# M102X.net
KiCad netlist of a schematic drawn in EAGLE
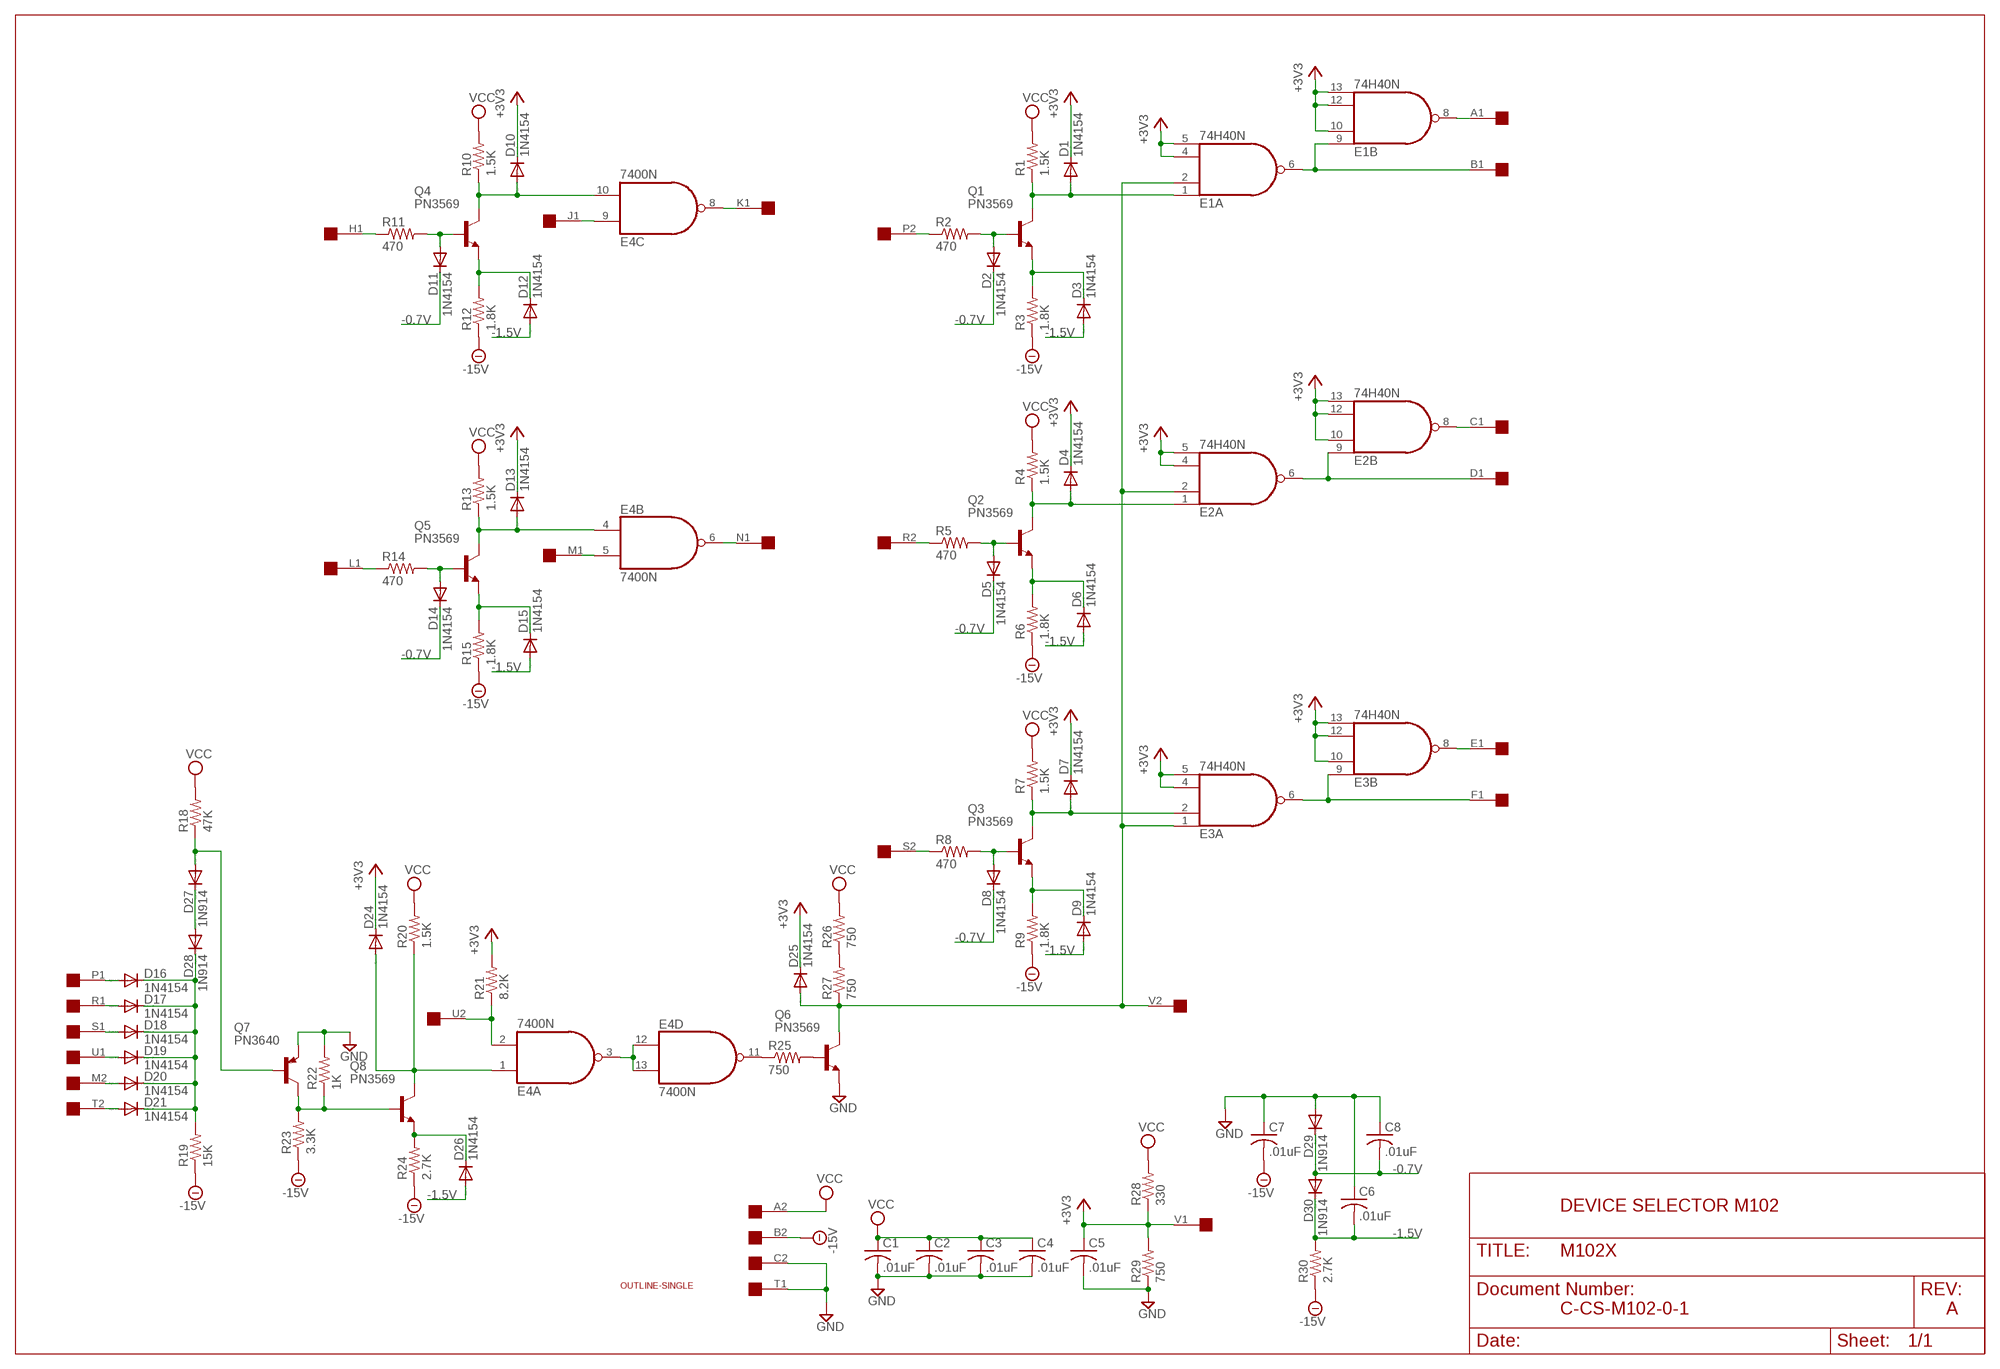
[diagram p0: schematic, sheet 1]

(export (version "E")
  (design (tool "Eeschema 10.0.6"))
  (components
    (comp (ref "C1")
      (value ".01uF")
      (footprint "eagle-import:C050-025X075")
      (libsource (lib "eagle-import") (part "C-US050-025X075"))
    )
    (comp (ref "C2")
      (value ".01uF")
      (footprint "eagle-import:C050-025X075")
      (libsource (lib "eagle-import") (part "C-US050-025X075"))
    )
    (comp (ref "C3")
      (value ".01uF")
      (footprint "eagle-import:C050-025X075")
      (libsource (lib "eagle-import") (part "C-US050-025X075"))
    )
    (comp (ref "C4")
      (value ".01uF")
      (footprint "eagle-import:C050-025X075")
      (libsource (lib "eagle-import") (part "C-US050-025X075"))
    )
    (comp (ref "C5")
      (value ".01uF")
      (footprint "eagle-import:C050-025X075")
      (libsource (lib "eagle-import") (part "C-US050-025X075"))
    )
    (comp (ref "C6")
      (value ".01uF")
      (footprint "eagle-import:C050-025X075")
      (libsource (lib "eagle-import") (part "C-US050-025X075"))
    )
    (comp (ref "C7")
      (value ".01uF")
      (footprint "eagle-import:C050-025X075")
      (libsource (lib "eagle-import") (part "C-US050-025X075"))
    )
    (comp (ref "C8")
      (value ".01uF")
      (footprint "eagle-import:C050-025X075")
      (libsource (lib "eagle-import") (part "C-US050-025X075"))
    )
    (comp (ref "D1")
      (value "1N4154")
      (footprint "eagle-import:DO35-10")
      (libsource (lib "eagle-import") (part "1N4148DO35-10"))
    )
    (comp (ref "D2")
      (value "1N4154")
      (footprint "eagle-import:DO35-10")
      (libsource (lib "eagle-import") (part "1N4148DO35-10"))
    )
    (comp (ref "D3")
      (value "1N4154")
      (footprint "eagle-import:DO35-10")
      (libsource (lib "eagle-import") (part "1N4148DO35-10"))
    )
    (comp (ref "D4")
      (value "1N4154")
      (footprint "eagle-import:DO35-10")
      (libsource (lib "eagle-import") (part "1N4148DO35-10"))
    )
    (comp (ref "D5")
      (value "1N4154")
      (footprint "eagle-import:DO35-10")
      (libsource (lib "eagle-import") (part "1N4148DO35-10"))
    )
    (comp (ref "D6")
      (value "1N4154")
      (footprint "eagle-import:DO35-10")
      (libsource (lib "eagle-import") (part "1N4148DO35-10"))
    )
    (comp (ref "D7")
      (value "1N4154")
      (footprint "eagle-import:DO35-10")
      (libsource (lib "eagle-import") (part "1N4148DO35-10"))
    )
    (comp (ref "D8")
      (value "1N4154")
      (footprint "eagle-import:DO35-10")
      (libsource (lib "eagle-import") (part "1N4148DO35-10"))
    )
    (comp (ref "D9")
      (value "1N4154")
      (footprint "eagle-import:DO35-10")
      (libsource (lib "eagle-import") (part "1N4148DO35-10"))
    )
    (comp (ref "D10")
      (value "1N4154")
      (footprint "eagle-import:DO35-10")
      (libsource (lib "eagle-import") (part "1N4148DO35-10"))
    )
    (comp (ref "D11")
      (value "1N4154")
      (footprint "eagle-import:DO35-10")
      (libsource (lib "eagle-import") (part "1N4148DO35-10"))
    )
    (comp (ref "D12")
      (value "1N4154")
      (footprint "eagle-import:DO35-10")
      (libsource (lib "eagle-import") (part "1N4148DO35-10"))
    )
    (comp (ref "D13")
      (value "1N4154")
      (footprint "eagle-import:DO35-10")
      (libsource (lib "eagle-import") (part "1N4148DO35-10"))
    )
    (comp (ref "D14")
      (value "1N4154")
      (footprint "eagle-import:DO35-10")
      (libsource (lib "eagle-import") (part "1N4148DO35-10"))
    )
    (comp (ref "D15")
      (value "1N4154")
      (footprint "eagle-import:DO35-10")
      (libsource (lib "eagle-import") (part "1N4148DO35-10"))
    )
    (comp (ref "D16")
      (value "1N4154")
      (footprint "eagle-import:DO35-10")
      (libsource (lib "eagle-import") (part "1N4148DO35-10"))
    )
    (comp (ref "D17")
      (value "1N4154")
      (footprint "eagle-import:DO35-10")
      (libsource (lib "eagle-import") (part "1N4148DO35-10"))
    )
    (comp (ref "D18")
      (value "1N4154")
      (footprint "eagle-import:DO35-10")
      (libsource (lib "eagle-import") (part "1N4148DO35-10"))
    )
    (comp (ref "D19")
      (value "1N4154")
      (footprint "eagle-import:DO35-10")
      (libsource (lib "eagle-import") (part "1N4148DO35-10"))
    )
    (comp (ref "D20")
      (value "1N4154")
      (footprint "eagle-import:DO35-10")
      (libsource (lib "eagle-import") (part "1N4148DO35-10"))
    )
    (comp (ref "D21")
      (value "1N4154")
      (footprint "eagle-import:DO35-10")
      (libsource (lib "eagle-import") (part "1N4148DO35-10"))
    )
    (comp (ref "D24")
      (value "1N4154")
      (footprint "eagle-import:DO35-10")
      (libsource (lib "eagle-import") (part "1N4148DO35-10"))
    )
    (comp (ref "D25")
      (value "1N4154")
      (footprint "eagle-import:DO35-10")
      (libsource (lib "eagle-import") (part "1N4148DO35-10"))
    )
    (comp (ref "D26")
      (value "1N4154")
      (footprint "eagle-import:DO35-10")
      (libsource (lib "eagle-import") (part "1N4148DO35-10"))
    )
    (comp (ref "D27")
      (value "1N914")
      (footprint "eagle-import:DO35-10")
      (libsource (lib "eagle-import") (part "1N4148DO35-10"))
    )
    (comp (ref "D28")
      (value "1N914")
      (footprint "eagle-import:DO35-10")
      (libsource (lib "eagle-import") (part "1N4148DO35-10"))
    )
    (comp (ref "D29")
      (value "1N914")
      (footprint "eagle-import:DO35-10")
      (libsource (lib "eagle-import") (part "1N4148DO35-10"))
    )
    (comp (ref "D30")
      (value "1N914")
      (footprint "eagle-import:DO35-10")
      (libsource (lib "eagle-import") (part "1N4148DO35-10"))
    )
    (comp (ref "E1")
      (value "74H40N")
      (footprint "eagle-import:DIL14")
      (libsource (lib "eagle-import") (part "7420NS"))
    )
    (comp (ref "E2")
      (value "74H40N")
      (footprint "eagle-import:DIL14")
      (libsource (lib "eagle-import") (part "7420NS"))
    )
    (comp (ref "E3")
      (value "74H40N")
      (footprint "eagle-import:DIL14")
      (libsource (lib "eagle-import") (part "7420NS"))
    )
    (comp (ref "E4")
      (value "7400N")
      (footprint "eagle-import:DIL14")
      (libsource (lib "eagle-import") (part "7400N"))
    )
    (comp (ref "Q1")
      (value "PN3569")
      (footprint "eagle-import:TO39")
      (libsource (lib "eagle-import") (part "-NPN-TO39-EBC2N1613"))
    )
    (comp (ref "Q2")
      (value "PN3569")
      (footprint "eagle-import:TO39")
      (libsource (lib "eagle-import") (part "-NPN-TO39-EBC2N1613"))
    )
    (comp (ref "Q3")
      (value "PN3569")
      (footprint "eagle-import:TO39")
      (libsource (lib "eagle-import") (part "-NPN-TO39-EBC2N1613"))
    )
    (comp (ref "Q4")
      (value "PN3569")
      (footprint "eagle-import:TO39")
      (libsource (lib "eagle-import") (part "-NPN-TO39-EBC2N1613"))
    )
    (comp (ref "Q5")
      (value "PN3569")
      (footprint "eagle-import:TO39")
      (libsource (lib "eagle-import") (part "-NPN-TO39-EBC2N1613"))
    )
    (comp (ref "Q6")
      (value "PN3569")
      (footprint "eagle-import:TO39")
      (libsource (lib "eagle-import") (part "-NPN-TO39-EBC2N1613"))
    )
    (comp (ref "Q7")
      (value "PN3640")
      (footprint "eagle-import:TO39")
      (libsource (lib "eagle-import") (part "-PNP-TO39-EBC2N3635"))
    )
    (comp (ref "Q8")
      (value "PN3569")
      (footprint "eagle-import:TO39")
      (libsource (lib "eagle-import") (part "-NPN-TO39-EBC2N1613"))
    )
    (comp (ref "R1")
      (value "1.5K")
      (footprint "eagle-import:0207_10")
      (libsource (lib "eagle-import") (part "R-US_0207/10"))
    )
    (comp (ref "R2")
      (value "470")
      (footprint "eagle-import:0207_10")
      (libsource (lib "eagle-import") (part "R-US_0207/10"))
    )
    (comp (ref "R3")
      (value "1.8K")
      (footprint "eagle-import:0207_10")
      (libsource (lib "eagle-import") (part "R-US_0207/10"))
    )
    (comp (ref "R4")
      (value "1.5K")
      (footprint "eagle-import:0207_10")
      (libsource (lib "eagle-import") (part "R-US_0207/10"))
    )
    (comp (ref "R5")
      (value "470")
      (footprint "eagle-import:0207_10")
      (libsource (lib "eagle-import") (part "R-US_0207/10"))
    )
    (comp (ref "R6")
      (value "1.8K")
      (footprint "eagle-import:0207_10")
      (libsource (lib "eagle-import") (part "R-US_0207/10"))
    )
    (comp (ref "R7")
      (value "1.5K")
      (footprint "eagle-import:0207_10")
      (libsource (lib "eagle-import") (part "R-US_0207/10"))
    )
    (comp (ref "R8")
      (value "470")
      (footprint "eagle-import:0207_10")
      (libsource (lib "eagle-import") (part "R-US_0207/10"))
    )
    (comp (ref "R9")
      (value "1.8K")
      (footprint "eagle-import:0207_10")
      (libsource (lib "eagle-import") (part "R-US_0207/10"))
    )
    (comp (ref "R10")
      (value "1.5K")
      (footprint "eagle-import:0207_10")
      (libsource (lib "eagle-import") (part "R-US_0207/10"))
    )
    (comp (ref "R11")
      (value "470")
      (footprint "eagle-import:0207_10")
      (libsource (lib "eagle-import") (part "R-US_0207/10"))
    )
    (comp (ref "R12")
      (value "1.8K")
      (footprint "eagle-import:0207_10")
      (libsource (lib "eagle-import") (part "R-US_0207/10"))
    )
    (comp (ref "R13")
      (value "1.5K")
      (footprint "eagle-import:0207_10")
      (libsource (lib "eagle-import") (part "R-US_0207/10"))
    )
    (comp (ref "R14")
      (value "470")
      (footprint "eagle-import:0207_10")
      (libsource (lib "eagle-import") (part "R-US_0207/10"))
    )
    (comp (ref "R15")
      (value "1.8K")
      (footprint "eagle-import:0207_10")
      (libsource (lib "eagle-import") (part "R-US_0207/10"))
    )
    (comp (ref "R18")
      (value "47K")
      (footprint "eagle-import:0207_10")
      (libsource (lib "eagle-import") (part "R-US_0207/10"))
    )
    (comp (ref "R19")
      (value "15K")
      (footprint "eagle-import:0207_10")
      (libsource (lib "eagle-import") (part "R-US_0207/10"))
    )
    (comp (ref "R20")
      (value "1.5K")
      (footprint "eagle-import:0207_10")
      (libsource (lib "eagle-import") (part "R-US_0207/10"))
    )
    (comp (ref "R21")
      (value "8.2K")
      (footprint "eagle-import:0207_10")
      (libsource (lib "eagle-import") (part "R-US_0207/10"))
    )
    (comp (ref "R22")
      (value "1K")
      (footprint "eagle-import:0207_10")
      (libsource (lib "eagle-import") (part "R-US_0207/10"))
    )
    (comp (ref "R23")
      (value "3.3K")
      (footprint "eagle-import:0207_10")
      (libsource (lib "eagle-import") (part "R-US_0207/10"))
    )
    (comp (ref "R24")
      (value "2.7K")
      (footprint "eagle-import:0207_10")
      (libsource (lib "eagle-import") (part "R-US_0207/10"))
    )
    (comp (ref "R25")
      (value "750")
      (footprint "eagle-import:0207_10")
      (libsource (lib "eagle-import") (part "R-US_0207/10"))
    )
    (comp (ref "R26")
      (value "750")
      (footprint "eagle-import:0207_10")
      (libsource (lib "eagle-import") (part "R-US_0207/10"))
    )
    (comp (ref "R27")
      (value "750")
      (footprint "eagle-import:0207_10")
      (libsource (lib "eagle-import") (part "R-US_0207/10"))
    )
    (comp (ref "R28")
      (value "330")
      (footprint "eagle-import:0207_10")
      (libsource (lib "eagle-import") (part "R-US_0207/10"))
    )
    (comp (ref "R29")
      (value "750")
      (footprint "eagle-import:0207_10")
      (libsource (lib "eagle-import") (part "R-US_0207/10"))
    )
    (comp (ref "R30")
      (value "2.7K")
      (footprint "eagle-import:0207_10")
      (libsource (lib "eagle-import") (part "R-US_0207/10"))
    )
    (comp (ref "U$8")
      (value "SINGLE")
      (footprint "eagle-import:EDGE-CON2")
      (libsource (lib "eagle-import") (part "SINGLE"))
    )
    (comp (ref "U$9")
      (value "OUTLINE-SINGLE")
      (footprint "eagle-import:SINGLE")
      (libsource (lib "eagle-import") (part "OUTLINE-SINGLE"))
    )
  )
  (nets
    (net (code "1") (name "+3V3") (class "Default")
      (node (ref "C5") (pin "1") (pinfunction "1_1") (pintype "passive"))
      (node (ref "D1") (pin "C") (pinfunction "C_C") (pintype "passive"))
      (node (ref "D10") (pin "C") (pinfunction "C_C") (pintype "passive"))
      (node (ref "D13") (pin "C") (pinfunction "C_C") (pintype "passive"))
      (node (ref "D24") (pin "C") (pinfunction "C_C") (pintype "passive"))
      (node (ref "D25") (pin "C") (pinfunction "C_C") (pintype "passive"))
      (node (ref "D4") (pin "C") (pinfunction "C_C") (pintype "passive"))
      (node (ref "D7") (pin "C") (pinfunction "C_C") (pintype "passive"))
      (node (ref "E1") (pin "10") (pinfunction "I1_10") (pintype "input"))
      (node (ref "E1") (pin "12") (pinfunction "I2_12") (pintype "input"))
      (node (ref "E1") (pin "13") (pinfunction "I3_13") (pintype "input"))
      (node (ref "E1") (pin "4") (pinfunction "I2_4") (pintype "input"))
      (node (ref "E1") (pin "5") (pinfunction "I3_5") (pintype "input"))
      (node (ref "E2") (pin "10") (pinfunction "I1_10") (pintype "input"))
      (node (ref "E2") (pin "12") (pinfunction "I2_12") (pintype "input"))
      (node (ref "E2") (pin "13") (pinfunction "I3_13") (pintype "input"))
      (node (ref "E2") (pin "4") (pinfunction "I2_4") (pintype "input"))
      (node (ref "E2") (pin "5") (pinfunction "I3_5") (pintype "input"))
      (node (ref "E3") (pin "10") (pinfunction "I1_10") (pintype "input"))
      (node (ref "E3") (pin "12") (pinfunction "I2_12") (pintype "input"))
      (node (ref "E3") (pin "13") (pinfunction "I3_13") (pintype "input"))
      (node (ref "E3") (pin "4") (pinfunction "I2_4") (pintype "input"))
      (node (ref "E3") (pin "5") (pinfunction "I3_5") (pintype "input"))
      (node (ref "R21") (pin "2") (pinfunction "2_2") (pintype "passive"))
      (node (ref "R28") (pin "1") (pinfunction "1_1") (pintype "passive"))
      (node (ref "R29") (pin "2") (pinfunction "2_2") (pintype "passive"))
      (node (ref "U$8") (pin "V1") (pinfunction "1_V1") (pintype "bidirectional"))
    )
    (net (code "2") (name "-15V") (class "Default")
      (node (ref "C7") (pin "2") (pinfunction "2_2") (pintype "passive"))
      (node (ref "R12") (pin "1") (pinfunction "1_1") (pintype "passive"))
      (node (ref "R15") (pin "1") (pinfunction "1_1") (pintype "passive"))
      (node (ref "R19") (pin "1") (pinfunction "1_1") (pintype "passive"))
      (node (ref "R23") (pin "1") (pinfunction "1_1") (pintype "passive"))
      (node (ref "R24") (pin "1") (pinfunction "1_1") (pintype "passive"))
      (node (ref "R3") (pin "1") (pinfunction "1_1") (pintype "passive"))
      (node (ref "R30") (pin "1") (pinfunction "1_1") (pintype "passive"))
      (node (ref "R6") (pin "1") (pinfunction "1_1") (pintype "passive"))
      (node (ref "R9") (pin "1") (pinfunction "1_1") (pintype "passive"))
      (node (ref "U$8") (pin "B2") (pinfunction "1_B2") (pintype "bidirectional"))
    )
    (net (code "3") (name "/-0.7V") (class "Default")
      (node (ref "C8") (pin "2") (pinfunction "2_2") (pintype "passive"))
      (node (ref "D11") (pin "C") (pinfunction "C_C") (pintype "passive"))
      (node (ref "D14") (pin "C") (pinfunction "C_C") (pintype "passive"))
      (node (ref "D2") (pin "C") (pinfunction "C_C") (pintype "passive"))
      (node (ref "D29") (pin "C") (pinfunction "C_C") (pintype "passive"))
      (node (ref "D30") (pin "A") (pinfunction "A_A") (pintype "passive"))
      (node (ref "D5") (pin "C") (pinfunction "C_C") (pintype "passive"))
      (node (ref "D8") (pin "C") (pinfunction "C_C") (pintype "passive"))
    )
    (net (code "4") (name "/-1.5V") (class "Default")
      (node (ref "C6") (pin "2") (pinfunction "2_2") (pintype "passive"))
      (node (ref "D12") (pin "A") (pinfunction "A_A") (pintype "passive"))
      (node (ref "D15") (pin "A") (pinfunction "A_A") (pintype "passive"))
      (node (ref "D26") (pin "A") (pinfunction "A_A") (pintype "passive"))
      (node (ref "D3") (pin "A") (pinfunction "A_A") (pintype "passive"))
      (node (ref "D30") (pin "C") (pinfunction "C_C") (pintype "passive"))
      (node (ref "D6") (pin "A") (pinfunction "A_A") (pintype "passive"))
      (node (ref "D9") (pin "A") (pinfunction "A_A") (pintype "passive"))
      (node (ref "R30") (pin "2") (pinfunction "2_2") (pintype "passive"))
    )
    (net (code "5") (name "GND") (class "Default")
      (node (ref "C1") (pin "2") (pinfunction "2_2") (pintype "passive"))
      (node (ref "C2") (pin "2") (pinfunction "2_2") (pintype "passive"))
      (node (ref "C3") (pin "2") (pinfunction "2_2") (pintype "passive"))
      (node (ref "C4") (pin "2") (pinfunction "2_2") (pintype "passive"))
      (node (ref "C5") (pin "2") (pinfunction "2_2") (pintype "passive"))
      (node (ref "C6") (pin "1") (pinfunction "1_1") (pintype "passive"))
      (node (ref "C7") (pin "1") (pinfunction "1_1") (pintype "passive"))
      (node (ref "C8") (pin "1") (pinfunction "1_1") (pintype "passive"))
      (node (ref "D29") (pin "A") (pinfunction "A_A") (pintype "passive"))
      (node (ref "Q6") (pin "1") (pinfunction "E_1") (pintype "passive"))
      (node (ref "Q7") (pin "1") (pinfunction "E_1") (pintype "passive"))
      (node (ref "R22") (pin "2") (pinfunction "2_2") (pintype "passive"))
      (node (ref "R29") (pin "1") (pinfunction "1_1") (pintype "passive"))
      (node (ref "U$8") (pin "C2") (pinfunction "1_C2") (pintype "bidirectional"))
      (node (ref "U$8") (pin "T1") (pinfunction "1_T1") (pintype "bidirectional"))
    )
    (net (code "6") (name "Net-(D16-PadC)") (class "Default")
      (node (ref "D16") (pin "C") (pinfunction "C_C") (pintype "passive"))
      (node (ref "D17") (pin "C") (pinfunction "C_C") (pintype "passive"))
      (node (ref "D18") (pin "C") (pinfunction "C_C") (pintype "passive"))
      (node (ref "D19") (pin "C") (pinfunction "C_C") (pintype "passive"))
      (node (ref "D20") (pin "C") (pinfunction "C_C") (pintype "passive"))
      (node (ref "D21") (pin "C") (pinfunction "C_C") (pintype "passive"))
      (node (ref "D28") (pin "C") (pinfunction "C_C") (pintype "passive"))
      (node (ref "R19") (pin "2") (pinfunction "2_2") (pintype "passive"))
    )
    (net (code "7") (name "Net-(D27-PadC)") (class "Default")
      (node (ref "D27") (pin "C") (pinfunction "C_C") (pintype "passive"))
      (node (ref "D28") (pin "A") (pinfunction "A_A") (pintype "passive"))
    )
    (net (code "8") (name "Net-(E1A-I0)") (class "Default")
      (node (ref "D1") (pin "A") (pinfunction "A_A") (pintype "passive"))
      (node (ref "E1") (pin "1") (pinfunction "I0_1") (pintype "input"))
      (node (ref "Q1") (pin "3") (pinfunction "C_3") (pintype "passive"))
      (node (ref "R1") (pin "1") (pinfunction "1_1") (pintype "passive"))
    )
    (net (code "9") (name "Net-(E1A-I1)") (class "Default")
      (node (ref "D25") (pin "A") (pinfunction "A_A") (pintype "passive"))
      (node (ref "E1") (pin "2") (pinfunction "I1_2") (pintype "input"))
      (node (ref "E2") (pin "2") (pinfunction "I1_2") (pintype "input"))
      (node (ref "E3") (pin "1") (pinfunction "I0_1") (pintype "input"))
      (node (ref "Q6") (pin "3") (pinfunction "C_3") (pintype "passive"))
      (node (ref "R27") (pin "1") (pinfunction "1_1") (pintype "passive"))
      (node (ref "U$8") (pin "V2") (pinfunction "1_V2") (pintype "bidirectional"))
    )
    (net (code "10") (name "Net-(E1A-O)") (class "Default")
      (node (ref "E1") (pin "6") (pinfunction "O_6") (pintype "output"))
      (node (ref "E1") (pin "9") (pinfunction "I0_9") (pintype "input"))
      (node (ref "U$8") (pin "B1") (pinfunction "1_B1") (pintype "bidirectional"))
    )
    (net (code "11") (name "Net-(E1B-O)") (class "Default")
      (node (ref "E1") (pin "8") (pinfunction "O_8") (pintype "output"))
      (node (ref "U$8") (pin "A1") (pinfunction "1_A1") (pintype "bidirectional"))
    )
    (net (code "12") (name "Net-(E2A-I0)") (class "Default")
      (node (ref "D4") (pin "A") (pinfunction "A_A") (pintype "passive"))
      (node (ref "E2") (pin "1") (pinfunction "I0_1") (pintype "input"))
      (node (ref "Q2") (pin "3") (pinfunction "C_3") (pintype "passive"))
      (node (ref "R4") (pin "1") (pinfunction "1_1") (pintype "passive"))
    )
    (net (code "13") (name "Net-(E2A-O)") (class "Default")
      (node (ref "E2") (pin "6") (pinfunction "O_6") (pintype "output"))
      (node (ref "E2") (pin "9") (pinfunction "I0_9") (pintype "input"))
      (node (ref "U$8") (pin "D1") (pinfunction "1_D1") (pintype "bidirectional"))
    )
    (net (code "14") (name "Net-(E2B-O)") (class "Default")
      (node (ref "E2") (pin "8") (pinfunction "O_8") (pintype "output"))
      (node (ref "U$8") (pin "C1") (pinfunction "1_C1") (pintype "bidirectional"))
    )
    (net (code "15") (name "Net-(E3A-I1)") (class "Default")
      (node (ref "D7") (pin "A") (pinfunction "A_A") (pintype "passive"))
      (node (ref "E3") (pin "2") (pinfunction "I1_2") (pintype "input"))
      (node (ref "Q3") (pin "3") (pinfunction "C_3") (pintype "passive"))
      (node (ref "R7") (pin "1") (pinfunction "1_1") (pintype "passive"))
    )
    (net (code "16") (name "Net-(E3A-O)") (class "Default")
      (node (ref "E3") (pin "6") (pinfunction "O_6") (pintype "output"))
      (node (ref "E3") (pin "9") (pinfunction "I0_9") (pintype "input"))
      (node (ref "U$8") (pin "F1") (pinfunction "1_F1") (pintype "bidirectional"))
    )
    (net (code "17") (name "Net-(E3B-O)") (class "Default")
      (node (ref "E3") (pin "8") (pinfunction "O_8") (pintype "output"))
      (node (ref "U$8") (pin "E1") (pinfunction "1_E1") (pintype "bidirectional"))
    )
    (net (code "18") (name "Net-(E4A-I0)") (class "Default")
      (node (ref "D24") (pin "A") (pinfunction "A_A") (pintype "passive"))
      (node (ref "E4") (pin "1") (pinfunction "I0_1") (pintype "input"))
      (node (ref "Q8") (pin "3") (pinfunction "C_3") (pintype "passive"))
      (node (ref "R20") (pin "1") (pinfunction "1_1") (pintype "passive"))
    )
    (net (code "19") (name "Net-(E4A-I1)") (class "Default")
      (node (ref "E4") (pin "2") (pinfunction "I1_2") (pintype "input"))
      (node (ref "R21") (pin "1") (pinfunction "1_1") (pintype "passive"))
      (node (ref "U$8") (pin "U2") (pinfunction "1_U2") (pintype "bidirectional"))
    )
    (net (code "20") (name "Net-(E4A-O)") (class "Default")
      (node (ref "E4") (pin "12") (pinfunction "I0_12") (pintype "input"))
      (node (ref "E4") (pin "13") (pinfunction "I1_13") (pintype "input"))
      (node (ref "E4") (pin "3") (pinfunction "O_3") (pintype "output"))
    )
    (net (code "21") (name "Net-(E4B-I0)") (class "Default")
      (node (ref "D13") (pin "A") (pinfunction "A_A") (pintype "passive"))
      (node (ref "E4") (pin "4") (pinfunction "I0_4") (pintype "input"))
      (node (ref "Q5") (pin "3") (pinfunction "C_3") (pintype "passive"))
      (node (ref "R13") (pin "1") (pinfunction "1_1") (pintype "passive"))
    )
    (net (code "22") (name "Net-(E4B-I1)") (class "Default")
      (node (ref "E4") (pin "5") (pinfunction "I1_5") (pintype "input"))
      (node (ref "U$8") (pin "M1") (pinfunction "1_M1") (pintype "bidirectional"))
    )
    (net (code "23") (name "Net-(E4B-O)") (class "Default")
      (node (ref "E4") (pin "6") (pinfunction "O_6") (pintype "output"))
      (node (ref "U$8") (pin "N1") (pinfunction "1_N1") (pintype "bidirectional"))
    )
    (net (code "24") (name "Net-(E4C-I0)") (class "Default")
      (node (ref "E4") (pin "9") (pinfunction "I0_9") (pintype "input"))
      (node (ref "U$8") (pin "J1") (pinfunction "1_J1") (pintype "bidirectional"))
    )
    (net (code "25") (name "Net-(E4C-I1)") (class "Default")
      (node (ref "D10") (pin "A") (pinfunction "A_A") (pintype "passive"))
      (node (ref "E4") (pin "10") (pinfunction "I1_10") (pintype "input"))
      (node (ref "Q4") (pin "3") (pinfunction "C_3") (pintype "passive"))
      (node (ref "R10") (pin "1") (pinfunction "1_1") (pintype "passive"))
    )
    (net (code "26") (name "Net-(E4C-O)") (class "Default")
      (node (ref "E4") (pin "8") (pinfunction "O_8") (pintype "output"))
      (node (ref "U$8") (pin "K1") (pinfunction "1_K1") (pintype "bidirectional"))
    )
    (net (code "27") (name "Net-(E4D-O)") (class "Default")
      (node (ref "E4") (pin "11") (pinfunction "O_11") (pintype "output"))
      (node (ref "R25") (pin "1") (pinfunction "1_1") (pintype "passive"))
    )
    (net (code "28") (name "Net-(Q1-B)") (class "Default")
      (node (ref "D2") (pin "A") (pinfunction "A_A") (pintype "passive"))
      (node (ref "Q1") (pin "2") (pinfunction "B_2") (pintype "passive"))
      (node (ref "R2") (pin "2") (pinfunction "2_2") (pintype "passive"))
    )
    (net (code "29") (name "Net-(Q1-E)") (class "Default")
      (node (ref "D3") (pin "C") (pinfunction "C_C") (pintype "passive"))
      (node (ref "Q1") (pin "1") (pinfunction "E_1") (pintype "passive"))
      (node (ref "R3") (pin "2") (pinfunction "2_2") (pintype "passive"))
    )
    (net (code "30") (name "Net-(Q2-B)") (class "Default")
      (node (ref "D5") (pin "A") (pinfunction "A_A") (pintype "passive"))
      (node (ref "Q2") (pin "2") (pinfunction "B_2") (pintype "passive"))
      (node (ref "R5") (pin "2") (pinfunction "2_2") (pintype "passive"))
    )
    (net (code "31") (name "Net-(Q2-E)") (class "Default")
      (node (ref "D6") (pin "C") (pinfunction "C_C") (pintype "passive"))
      (node (ref "Q2") (pin "1") (pinfunction "E_1") (pintype "passive"))
      (node (ref "R6") (pin "2") (pinfunction "2_2") (pintype "passive"))
    )
    (net (code "32") (name "Net-(Q3-B)") (class "Default")
      (node (ref "D8") (pin "A") (pinfunction "A_A") (pintype "passive"))
      (node (ref "Q3") (pin "2") (pinfunction "B_2") (pintype "passive"))
      (node (ref "R8") (pin "2") (pinfunction "2_2") (pintype "passive"))
    )
    (net (code "33") (name "Net-(Q3-E)") (class "Default")
      (node (ref "D9") (pin "C") (pinfunction "C_C") (pintype "passive"))
      (node (ref "Q3") (pin "1") (pinfunction "E_1") (pintype "passive"))
      (node (ref "R9") (pin "2") (pinfunction "2_2") (pintype "passive"))
    )
    (net (code "34") (name "Net-(Q4-B)") (class "Default")
      (node (ref "D11") (pin "A") (pinfunction "A_A") (pintype "passive"))
      (node (ref "Q4") (pin "2") (pinfunction "B_2") (pintype "passive"))
      (node (ref "R11") (pin "2") (pinfunction "2_2") (pintype "passive"))
    )
    (net (code "35") (name "Net-(Q4-E)") (class "Default")
      (node (ref "D12") (pin "C") (pinfunction "C_C") (pintype "passive"))
      (node (ref "Q4") (pin "1") (pinfunction "E_1") (pintype "passive"))
      (node (ref "R12") (pin "2") (pinfunction "2_2") (pintype "passive"))
    )
    (net (code "36") (name "Net-(Q5-B)") (class "Default")
      (node (ref "D14") (pin "A") (pinfunction "A_A") (pintype "passive"))
      (node (ref "Q5") (pin "2") (pinfunction "B_2") (pintype "passive"))
      (node (ref "R14") (pin "2") (pinfunction "2_2") (pintype "passive"))
    )
    (net (code "37") (name "Net-(Q5-E)") (class "Default")
      (node (ref "D15") (pin "C") (pinfunction "C_C") (pintype "passive"))
      (node (ref "Q5") (pin "1") (pinfunction "E_1") (pintype "passive"))
      (node (ref "R15") (pin "2") (pinfunction "2_2") (pintype "passive"))
    )
    (net (code "38") (name "Net-(Q6-B)") (class "Default")
      (node (ref "Q6") (pin "2") (pinfunction "B_2") (pintype "passive"))
      (node (ref "R25") (pin "2") (pinfunction "2_2") (pintype "passive"))
    )
    (net (code "39") (name "Net-(Q7-B)") (class "Default")
      (node (ref "D27") (pin "A") (pinfunction "A_A") (pintype "passive"))
      (node (ref "Q7") (pin "2") (pinfunction "B_2") (pintype "passive"))
      (node (ref "R18") (pin "1") (pinfunction "1_1") (pintype "passive"))
    )
    (net (code "40") (name "Net-(Q7-C)") (class "Default")
      (node (ref "Q7") (pin "3") (pinfunction "C_3") (pintype "passive"))
      (node (ref "Q8") (pin "2") (pinfunction "B_2") (pintype "passive"))
      (node (ref "R22") (pin "1") (pinfunction "1_1") (pintype "passive"))
      (node (ref "R23") (pin "2") (pinfunction "2_2") (pintype "passive"))
    )
    (net (code "41") (name "Net-(Q8-E)") (class "Default")
      (node (ref "D26") (pin "C") (pinfunction "C_C") (pintype "passive"))
      (node (ref "Q8") (pin "1") (pinfunction "E_1") (pintype "passive"))
      (node (ref "R24") (pin "2") (pinfunction "2_2") (pintype "passive"))
    )
    (net (code "42") (name "Net-(R26-Pad1)") (class "Default")
      (node (ref "R26") (pin "1") (pinfunction "1_1") (pintype "passive"))
      (node (ref "R27") (pin "2") (pinfunction "2_2") (pintype "passive"))
    )
    (net (code "43") (name "Net-(U$8AA-1)") (class "Default")
      (node (ref "D17") (pin "A") (pinfunction "A_A") (pintype "passive"))
      (node (ref "U$8") (pin "R1") (pinfunction "1_R1") (pintype "bidirectional"))
    )
    (net (code "44") (name "Net-(U$8AB-1)") (class "Default")
      (node (ref "R5") (pin "1") (pinfunction "1_1") (pintype "passive"))
      (node (ref "U$8") (pin "R2") (pinfunction "1_R2") (pintype "bidirectional"))
    )
    (net (code "45") (name "Net-(U$8AC-1)") (class "Default")
      (node (ref "D18") (pin "A") (pinfunction "A_A") (pintype "passive"))
      (node (ref "U$8") (pin "S1") (pinfunction "1_S1") (pintype "bidirectional"))
    )
    (net (code "46") (name "Net-(U$8AD-1)") (class "Default")
      (node (ref "R8") (pin "1") (pinfunction "1_1") (pintype "passive"))
      (node (ref "U$8") (pin "S2") (pinfunction "1_S2") (pintype "bidirectional"))
    )
    (net (code "47") (name "Net-(U$8AF-1)") (class "Default")
      (node (ref "D21") (pin "A") (pinfunction "A_A") (pintype "passive"))
      (node (ref "U$8") (pin "T2") (pinfunction "1_T2") (pintype "bidirectional"))
    )
    (net (code "48") (name "Net-(U$8AG-1)") (class "Default")
      (node (ref "D19") (pin "A") (pinfunction "A_A") (pintype "passive"))
      (node (ref "U$8") (pin "U1") (pinfunction "1_U1") (pintype "bidirectional"))
    )
    (net (code "49") (name "Net-(U$8M-1)") (class "Default")
      (node (ref "R11") (pin "1") (pinfunction "1_1") (pintype "passive"))
      (node (ref "U$8") (pin "H1") (pinfunction "1_H1") (pintype "bidirectional"))
    )
    (net (code "50") (name "Net-(U$8S-1)") (class "Default")
      (node (ref "R14") (pin "1") (pinfunction "1_1") (pintype "passive"))
      (node (ref "U$8") (pin "L1") (pinfunction "1_L1") (pintype "bidirectional"))
    )
    (net (code "51") (name "Net-(U$8V-1)") (class "Default")
      (node (ref "D20") (pin "A") (pinfunction "A_A") (pintype "passive"))
      (node (ref "U$8") (pin "M2") (pinfunction "1_M2") (pintype "bidirectional"))
    )
    (net (code "52") (name "Net-(U$8Y-1)") (class "Default")
      (node (ref "D16") (pin "A") (pinfunction "A_A") (pintype "passive"))
      (node (ref "U$8") (pin "P1") (pinfunction "1_P1") (pintype "bidirectional"))
    )
    (net (code "53") (name "Net-(U$8Z-1)") (class "Default")
      (node (ref "R2") (pin "1") (pinfunction "1_1") (pintype "passive"))
      (node (ref "U$8") (pin "P2") (pinfunction "1_P2") (pintype "bidirectional"))
    )
    (net (code "54") (name "VCC") (class "Default")
      (node (ref "C1") (pin "1") (pinfunction "1_1") (pintype "passive"))
      (node (ref "C2") (pin "1") (pinfunction "1_1") (pintype "passive"))
      (node (ref "C3") (pin "1") (pinfunction "1_1") (pintype "passive"))
      (node (ref "C4") (pin "1") (pinfunction "1_1") (pintype "passive"))
      (node (ref "R1") (pin "2") (pinfunction "2_2") (pintype "passive"))
      (node (ref "R10") (pin "2") (pinfunction "2_2") (pintype "passive"))
      (node (ref "R13") (pin "2") (pinfunction "2_2") (pintype "passive"))
      (node (ref "R18") (pin "2") (pinfunction "2_2") (pintype "passive"))
      (node (ref "R20") (pin "2") (pinfunction "2_2") (pintype "passive"))
      (node (ref "R26") (pin "2") (pinfunction "2_2") (pintype "passive"))
      (node (ref "R28") (pin "2") (pinfunction "2_2") (pintype "passive"))
      (node (ref "R4") (pin "2") (pinfunction "2_2") (pintype "passive"))
      (node (ref "R7") (pin "2") (pinfunction "2_2") (pintype "passive"))
      (node (ref "U$8") (pin "A2") (pinfunction "1_A2") (pintype "bidirectional"))
    )
  )
)
